# serial_1.net
KiCad netlist of a schematic drawn in Altium Designer
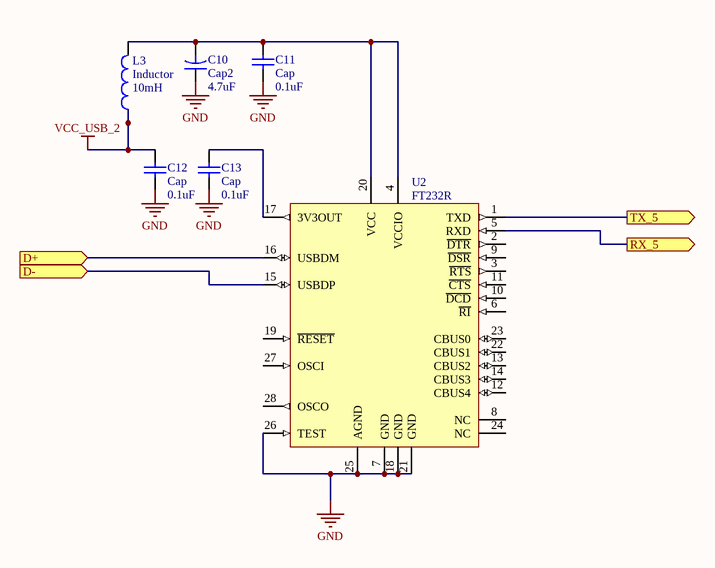
[diagram p0: serial_1.SchDoc]

(export (version "E")
  (design (tool "Eeschema 10.0.6"))
  (components
    (comp (ref "C10")
      (value "Cap2")
      (footprint "CAPR5-4X5")
      (description "Capacitor")
      (fields (field (name "ALTIUM_VALUE") "4.7uF") (field (name "PUBLISHER") "Altium Limited"))
      (libsource (lib "Miscellaneous Devices") (part "Cap2"))
    )
    (comp (ref "C11")
      (value "Cap")
      (footprint "C0805")
      (description "Capacitor")
      (fields (field (name "ALTIUM_VALUE") "0.1uF") (field (name "PUBLISHER") "Altium Limited"))
      (libsource (lib "Miscellaneous Devices") (part "Cap"))
    )
    (comp (ref "C12")
      (value "Cap")
      (footprint "C0805")
      (description "Capacitor")
      (fields (field (name "ALTIUM_VALUE") "0.1uF") (field (name "PUBLISHER") "Altium Limited"))
      (libsource (lib "Miscellaneous Devices") (part "Cap"))
    )
    (comp (ref "C13")
      (value "Cap")
      (footprint "C0805")
      (description "Capacitor")
      (fields (field (name "ALTIUM_VALUE") "0.1uF") (field (name "PUBLISHER") "Altium Limited"))
      (libsource (lib "Miscellaneous Devices") (part "Cap"))
    )
    (comp (ref "L3")
      (value "Inductor")
      (footprint "C0805")
      (fields (field (name "ALTIUM_VALUE") "10mH") (field (name "PUBLISHER") "Altium Limited"))
      (libsource (lib "Miscellaneous Devices") (part "Inductor"))
    )
    (comp (ref "U2")
      (value "FT232R")
      (footprint "SSOP-28_N")
      (description "USB UART Asynchronous Serial Data Transfer Chip, SSOP-28, Tray")
      (fields (field (name "PUBLISHER") "Altium Limited"))
      (libsource (lib "FTDI Communication UART") (part "FT232RL-Tray"))
    )
  )
  (nets
    (net (code "1") (name "/D+") (class "Default")
      (node (ref "U2") (pin "16") (pinfunction "USBDM_16") (pintype "bidirectional"))
    )
    (net (code "2") (name "/D-") (class "Default")
      (node (ref "U2") (pin "15") (pinfunction "USBDP_15") (pintype "bidirectional"))
    )
    (net (code "3") (name "/RX_5") (class "Default")
      (node (ref "U2") (pin "5") (pinfunction "RXD_5") (pintype "input"))
    )
    (net (code "4") (name "/TX_5") (class "Default")
      (node (ref "U2") (pin "1") (pinfunction "TXD_1") (pintype "output"))
    )
    (net (code "5") (name "GND") (class "Default")
      (node (ref "C10") (pin "1") (pinfunction "1_1") (pintype "passive"))
      (node (ref "C11") (pin "1") (pinfunction "1_1") (pintype "passive"))
      (node (ref "C12") (pin "1") (pinfunction "1_1") (pintype "passive"))
      (node (ref "C13") (pin "1") (pinfunction "1_1") (pintype "passive"))
      (node (ref "U2") (pin "18") (pinfunction "GND_18") (pintype "power_in"))
      (node (ref "U2") (pin "21") (pinfunction "GND_21") (pintype "power_in"))
      (node (ref "U2") (pin "25") (pinfunction "AGND_25") (pintype "power_in"))
      (node (ref "U2") (pin "26") (pinfunction "TEST_26") (pintype "input"))
      (node (ref "U2") (pin "7") (pinfunction "GND_7") (pintype "power_in"))
    )
    (net (code "6") (name "Net-(U2-3V3OUT)") (class "Default")
      (node (ref "C13") (pin "2") (pinfunction "2_2") (pintype "passive"))
      (node (ref "U2") (pin "17") (pinfunction "3V3OUT_17") (pintype "output"))
    )
    (net (code "7") (name "Net-(U2-VCC)") (class "Default")
      (node (ref "C10") (pin "2") (pinfunction "2_2") (pintype "passive"))
      (node (ref "C11") (pin "2") (pinfunction "2_2") (pintype "passive"))
      (node (ref "L3") (pin "2") (pinfunction "2_2") (pintype "passive"))
      (node (ref "U2") (pin "20") (pinfunction "VCC_20") (pintype "power_in"))
      (node (ref "U2") (pin "4") (pinfunction "VCCIO_4") (pintype "power_in"))
    )
    (net (code "8") (name "VCC_USB_2") (class "Default")
      (node (ref "C12") (pin "2") (pinfunction "2_2") (pintype "passive"))
      (node (ref "L3") (pin "1") (pinfunction "1_1") (pintype "passive"))
    )
    (net (code "9") (name "unconnected-(U2-CBUS0-Pad23)") (class "Default")
      (node (ref "U2") (pin "23") (pinfunction "CBUS0_23") (pintype "bidirectional"))
    )
    (net (code "10") (name "unconnected-(U2-CBUS1-Pad22)") (class "Default")
      (node (ref "U2") (pin "22") (pinfunction "CBUS1_22") (pintype "bidirectional"))
    )
    (net (code "11") (name "unconnected-(U2-CBUS2-Pad13)") (class "Default")
      (node (ref "U2") (pin "13") (pinfunction "CBUS2_13") (pintype "bidirectional"))
    )
    (net (code "12") (name "unconnected-(U2-CBUS3-Pad14)") (class "Default")
      (node (ref "U2") (pin "14") (pinfunction "CBUS3_14") (pintype "bidirectional"))
    )
    (net (code "13") (name "unconnected-(U2-CBUS4-Pad12)") (class "Default")
      (node (ref "U2") (pin "12") (pinfunction "CBUS4_12") (pintype "bidirectional"))
    )
    (net (code "14") (name "unconnected-(U2-NC-Pad8)") (class "Default")
      (node (ref "U2") (pin "8") (pinfunction "NC_8") (pintype "passive"))
    )
    (net (code "15") (name "unconnected-(U2-NC-Pad24)") (class "Default")
      (node (ref "U2") (pin "24") (pinfunction "NC_24") (pintype "passive"))
    )
    (net (code "16") (name "unconnected-(U2-OSCI-Pad27)") (class "Default")
      (node (ref "U2") (pin "27") (pinfunction "OSCI_27") (pintype "input"))
    )
    (net (code "17") (name "unconnected-(U2-OSCO-Pad28)") (class "Default")
      (node (ref "U2") (pin "28") (pinfunction "OSCO_28") (pintype "output"))
    )
    (net (code "18") (name "unconnected-(U2-~{CTS}-Pad11)") (class "Default")
      (node (ref "U2") (pin "11") (pinfunction "~{CTS}_11") (pintype "input"))
    )
    (net (code "19") (name "unconnected-(U2-~{DCD}-Pad10)") (class "Default")
      (node (ref "U2") (pin "10") (pinfunction "~{DCD}_10") (pintype "input"))
    )
    (net (code "20") (name "unconnected-(U2-~{DSR}-Pad9)") (class "Default")
      (node (ref "U2") (pin "9") (pinfunction "~{DSR}_9") (pintype "input"))
    )
    (net (code "21") (name "unconnected-(U2-~{DTR}-Pad2)") (class "Default")
      (node (ref "U2") (pin "2") (pinfunction "~{DTR}_2") (pintype "output"))
    )
    (net (code "22") (name "unconnected-(U2-~{RESET}-Pad19)") (class "Default")
      (node (ref "U2") (pin "19") (pinfunction "~{RESET}_19") (pintype "input"))
    )
    (net (code "23") (name "unconnected-(U2-~{RI}-Pad6)") (class "Default")
      (node (ref "U2") (pin "6") (pinfunction "~{RI}_6") (pintype "input"))
    )
    (net (code "24") (name "unconnected-(U2-~{RTS}-Pad3)") (class "Default")
      (node (ref "U2") (pin "3") (pinfunction "~{RTS}_3") (pintype "output"))
    )
  )
)
